# USBBridge3150.net
KiCad netlist of a schematic drawn in Altium Designer
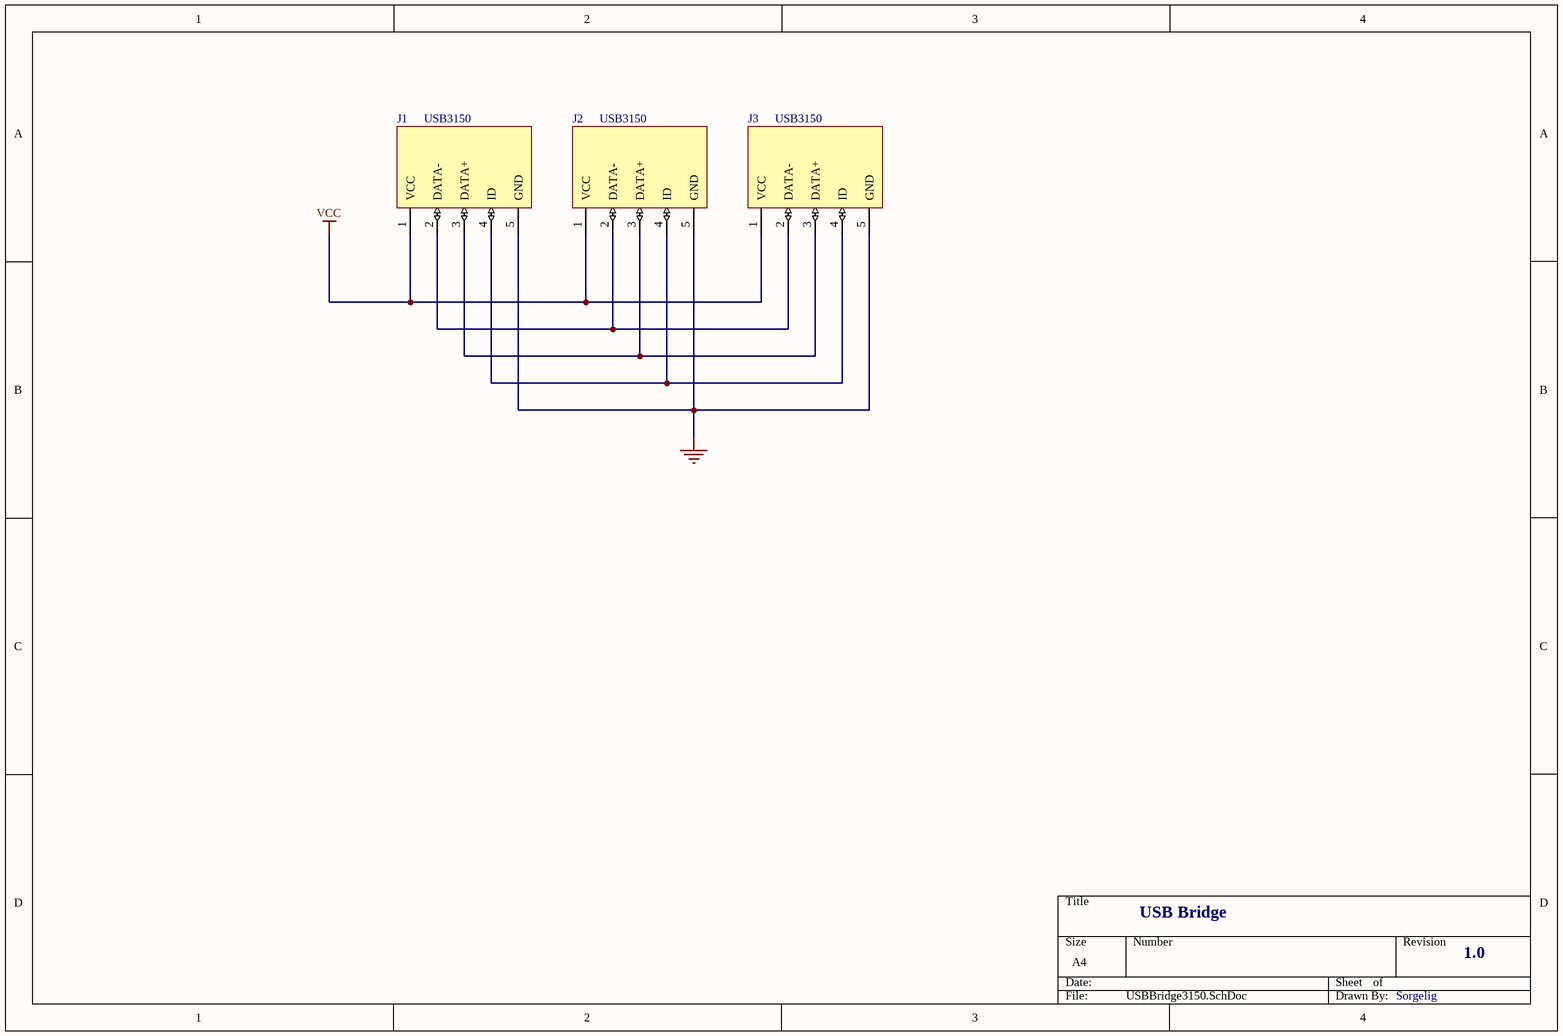
[diagram p0: USBBridge3150.SchDoc]

(export (version "E")
  (design (tool "Eeschema 10.0.6"))
  (components
    (comp (ref "J1")
      (value "USB3150")
      (footprint "USB3150")
      (description "Micro USB Plug, Type B, Through-Hole, Vertical,  with Shell Stakes, with Locating Pegs")
      (libsource (lib "lib") (part "USB3150-XX-XXX-X_revA"))
    )
    (comp (ref "J2")
      (value "USB3150")
      (footprint "USB3150")
      (description "Micro USB Plug, Type B, Through-Hole, Vertical,  with Shell Stakes, with Locating Pegs")
      (libsource (lib "lib") (part "USB3150-XX-XXX-X_revA"))
    )
    (comp (ref "J3")
      (value "USB3150")
      (footprint "USB3150")
      (description "Micro USB Plug, Type B, Through-Hole, Vertical,  with Shell Stakes, with Locating Pegs")
      (libsource (lib "lib") (part "USB3150-XX-XXX-X_revA"))
    )
  )
  (nets
    (net (code "1") (name "GND") (class "Default")
      (node (ref "J1") (pin "5") (pinfunction "GND_5") (pintype "power_in"))
      (node (ref "J2") (pin "5") (pinfunction "GND_5") (pintype "power_in"))
      (node (ref "J3") (pin "5") (pinfunction "GND_5") (pintype "power_in"))
    )
    (net (code "2") (name "Net-(J1-DATA+)") (class "Default")
      (node (ref "J1") (pin "3") (pinfunction "DATA+_3") (pintype "bidirectional"))
      (node (ref "J2") (pin "3") (pinfunction "DATA+_3") (pintype "bidirectional"))
      (node (ref "J3") (pin "3") (pinfunction "DATA+_3") (pintype "bidirectional"))
    )
    (net (code "3") (name "Net-(J1-DATA-)") (class "Default")
      (node (ref "J1") (pin "2") (pinfunction "DATA-_2") (pintype "bidirectional"))
      (node (ref "J2") (pin "2") (pinfunction "DATA-_2") (pintype "bidirectional"))
      (node (ref "J3") (pin "2") (pinfunction "DATA-_2") (pintype "bidirectional"))
    )
    (net (code "4") (name "Net-(J1-ID)") (class "Default")
      (node (ref "J1") (pin "4") (pinfunction "ID_4") (pintype "bidirectional"))
      (node (ref "J2") (pin "4") (pinfunction "ID_4") (pintype "bidirectional"))
      (node (ref "J3") (pin "4") (pinfunction "ID_4") (pintype "bidirectional"))
    )
    (net (code "5") (name "VCC") (class "Default")
      (node (ref "J1") (pin "1") (pinfunction "VCC_1") (pintype "power_in"))
      (node (ref "J2") (pin "1") (pinfunction "VCC_1") (pintype "power_in"))
      (node (ref "J3") (pin "1") (pinfunction "VCC_1") (pintype "power_in"))
    )
  )
)
